# F28335_AddOn_Memory.net
KiCad netlist of a schematic drawn in Altium Designer
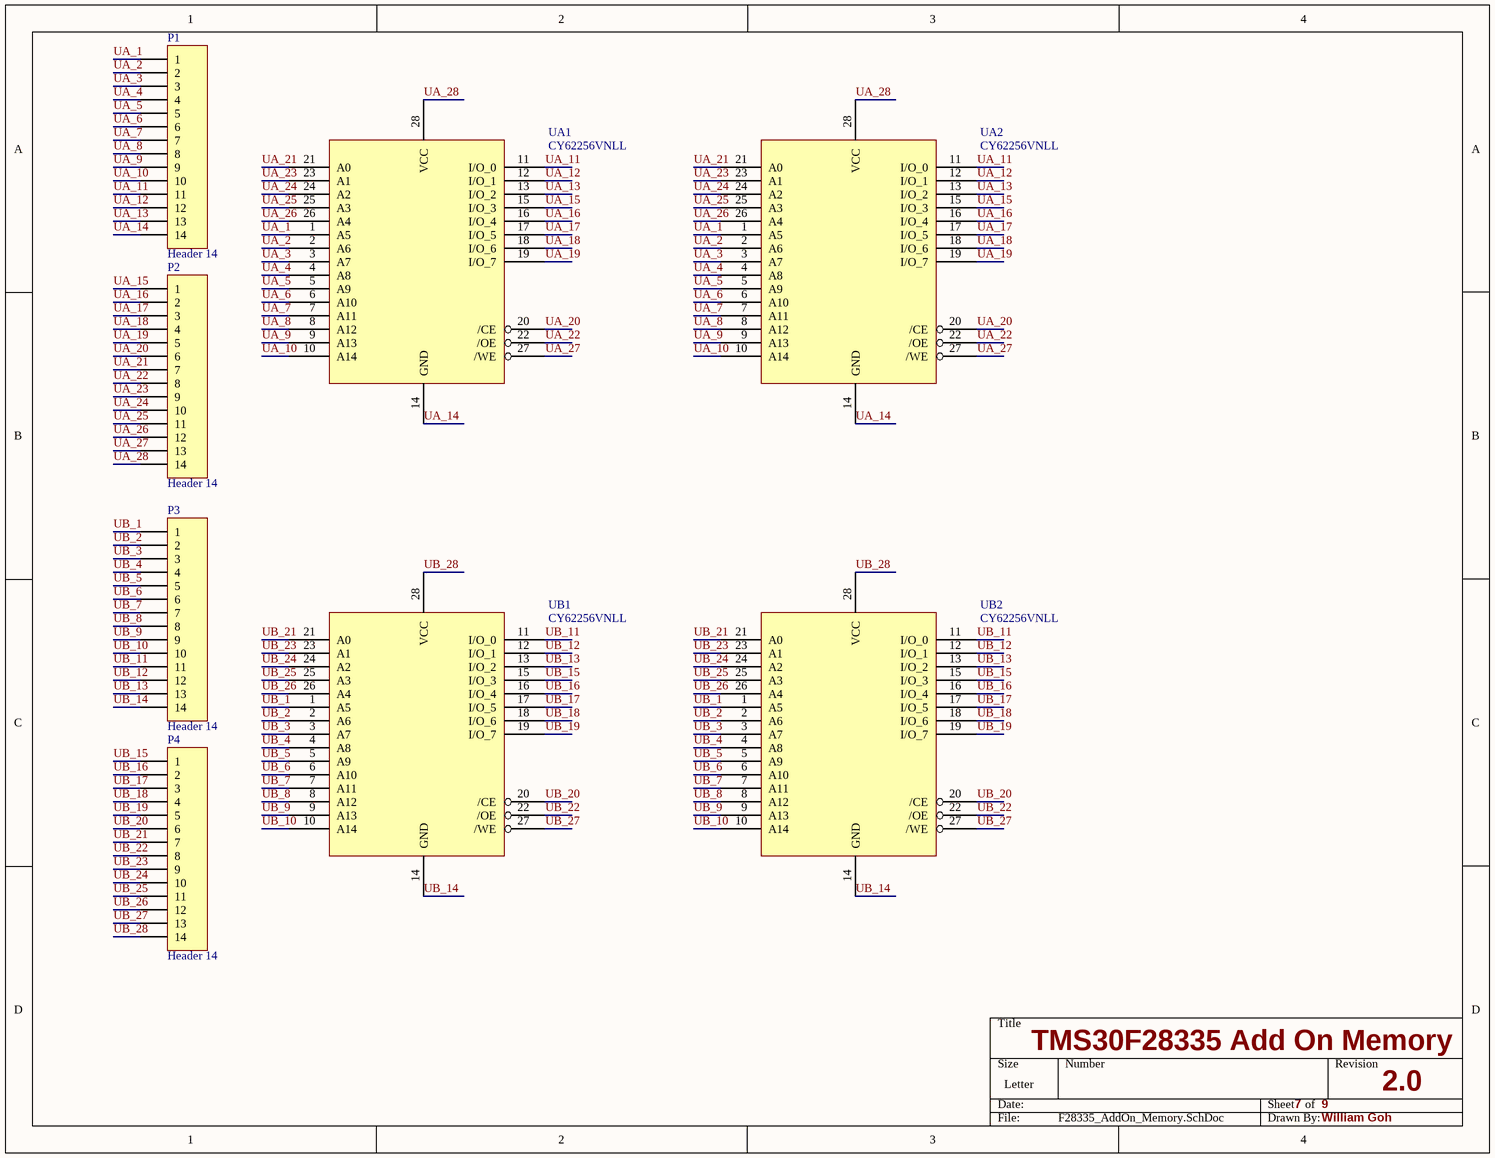
[diagram p0: F28335_AddOn_Memory.SchDoc]

(export (version "E")
  (design (tool "Eeschema 10.0.6"))
  (components
    (comp (ref "P1")
      (value "Header 14")
      (footprint "HDR1X14")
      (description "Header, 14-Pin")
      (fields (field (name "PUBLISHER") "Altium Limited"))
      (libsource (lib "Miscellaneous Connectors") (part "Header 14"))
    )
    (comp (ref "P2")
      (value "Header 14")
      (footprint "HDR1X14")
      (description "Header, 14-Pin")
      (fields (field (name "PUBLISHER") "Altium Limited"))
      (libsource (lib "Miscellaneous Connectors") (part "Header 14"))
    )
    (comp (ref "P3")
      (value "Header 14")
      (footprint "HDR1X14")
      (description "Header, 14-Pin")
      (fields (field (name "PUBLISHER") "Altium Limited"))
      (libsource (lib "Miscellaneous Connectors") (part "Header 14"))
    )
    (comp (ref "P4")
      (value "Header 14")
      (footprint "HDR1X14")
      (description "Header, 14-Pin")
      (fields (field (name "PUBLISHER") "Altium Limited"))
      (libsource (lib "Miscellaneous Connectors") (part "Header 14"))
    )
    (comp (ref "UA1")
      (value "CY62256VNLL")
      (footprint "28-SOIC CY62256VNLL")
      (description "Cypress SRAM 256KB 3.3V")
      (libsource (lib "F28335_DSC_Breakout") (part "CY62256VNLL"))
    )
    (comp (ref "UA2")
      (value "CY62256VNLL")
      (footprint "28-TSSOP CY62256VNLL")
      (description "Cypress SRAM 256KB 3.3V")
      (libsource (lib "F28335_DSC_Breakout") (part "CY62256VNLL"))
    )
    (comp (ref "UB1")
      (value "CY62256VNLL")
      (footprint "28-SOIC CY62256VNLL")
      (description "Cypress SRAM 256KB 3.3V")
      (libsource (lib "F28335_DSC_Breakout") (part "CY62256VNLL"))
    )
    (comp (ref "UB2")
      (value "CY62256VNLL")
      (footprint "28-TSSOP CY62256VNLL")
      (description "Cypress SRAM 256KB 3.3V")
      (libsource (lib "F28335_DSC_Breakout") (part "CY62256VNLL"))
    )
  )
  (nets
    (net (code "1") (name "/UA_1") (class "Default")
      (node (ref "P1") (pin "1") (pinfunction "1_1") (pintype "passive"))
      (node (ref "UA1") (pin "1") (pinfunction "A5_1") (pintype "passive"))
      (node (ref "UA2") (pin "1") (pinfunction "A5_1") (pintype "passive"))
    )
    (net (code "2") (name "/UA_2") (class "Default")
      (node (ref "P1") (pin "2") (pinfunction "2_2") (pintype "passive"))
      (node (ref "UA1") (pin "2") (pinfunction "A6_2") (pintype "passive"))
      (node (ref "UA2") (pin "2") (pinfunction "A6_2") (pintype "passive"))
    )
    (net (code "3") (name "/UA_3") (class "Default")
      (node (ref "P1") (pin "3") (pinfunction "3_3") (pintype "passive"))
      (node (ref "UA1") (pin "3") (pinfunction "A7_3") (pintype "passive"))
      (node (ref "UA2") (pin "3") (pinfunction "A7_3") (pintype "passive"))
    )
    (net (code "4") (name "/UA_4") (class "Default")
      (node (ref "P1") (pin "4") (pinfunction "4_4") (pintype "passive"))
      (node (ref "UA1") (pin "4") (pinfunction "A8_4") (pintype "passive"))
      (node (ref "UA2") (pin "4") (pinfunction "A8_4") (pintype "passive"))
    )
    (net (code "5") (name "/UA_5") (class "Default")
      (node (ref "P1") (pin "5") (pinfunction "5_5") (pintype "passive"))
      (node (ref "UA1") (pin "5") (pinfunction "A9_5") (pintype "passive"))
      (node (ref "UA2") (pin "5") (pinfunction "A9_5") (pintype "passive"))
    )
    (net (code "6") (name "/UA_6") (class "Default")
      (node (ref "P1") (pin "6") (pinfunction "6_6") (pintype "passive"))
      (node (ref "UA1") (pin "6") (pinfunction "A10_6") (pintype "passive"))
      (node (ref "UA2") (pin "6") (pinfunction "A10_6") (pintype "passive"))
    )
    (net (code "7") (name "/UA_7") (class "Default")
      (node (ref "P1") (pin "7") (pinfunction "7_7") (pintype "passive"))
      (node (ref "UA1") (pin "7") (pinfunction "A11_7") (pintype "passive"))
      (node (ref "UA2") (pin "7") (pinfunction "A11_7") (pintype "passive"))
    )
    (net (code "8") (name "/UA_8") (class "Default")
      (node (ref "P1") (pin "8") (pinfunction "8_8") (pintype "passive"))
      (node (ref "UA1") (pin "8") (pinfunction "A12_8") (pintype "passive"))
      (node (ref "UA2") (pin "8") (pinfunction "A12_8") (pintype "passive"))
    )
    (net (code "9") (name "/UA_9") (class "Default")
      (node (ref "P1") (pin "9") (pinfunction "9_9") (pintype "passive"))
      (node (ref "UA1") (pin "9") (pinfunction "A13_9") (pintype "passive"))
      (node (ref "UA2") (pin "9") (pinfunction "A13_9") (pintype "passive"))
    )
    (net (code "10") (name "/UA_10") (class "Default")
      (node (ref "P1") (pin "10") (pinfunction "10_10") (pintype "passive"))
      (node (ref "UA1") (pin "10") (pinfunction "A14_10") (pintype "passive"))
      (node (ref "UA2") (pin "10") (pinfunction "A14_10") (pintype "passive"))
    )
    (net (code "11") (name "/UA_11") (class "Default")
      (node (ref "P1") (pin "11") (pinfunction "11_11") (pintype "passive"))
      (node (ref "UA1") (pin "11") (pinfunction "I/O_0_11") (pintype "passive"))
      (node (ref "UA2") (pin "11") (pinfunction "I/O_0_11") (pintype "passive"))
    )
    (net (code "12") (name "/UA_12") (class "Default")
      (node (ref "P1") (pin "12") (pinfunction "12_12") (pintype "passive"))
      (node (ref "UA1") (pin "12") (pinfunction "I/O_1_12") (pintype "passive"))
      (node (ref "UA2") (pin "12") (pinfunction "I/O_1_12") (pintype "passive"))
    )
    (net (code "13") (name "/UA_13") (class "Default")
      (node (ref "P1") (pin "13") (pinfunction "13_13") (pintype "passive"))
      (node (ref "UA1") (pin "13") (pinfunction "I/O_2_13") (pintype "passive"))
      (node (ref "UA2") (pin "13") (pinfunction "I/O_2_13") (pintype "passive"))
    )
    (net (code "14") (name "/UA_14") (class "Default")
      (node (ref "P1") (pin "14") (pinfunction "14_14") (pintype "passive"))
      (node (ref "UA1") (pin "14") (pinfunction "GND_14") (pintype "passive"))
      (node (ref "UA2") (pin "14") (pinfunction "GND_14") (pintype "passive"))
    )
    (net (code "15") (name "/UA_15") (class "Default")
      (node (ref "P2") (pin "1") (pinfunction "1_1") (pintype "passive"))
      (node (ref "UA1") (pin "15") (pinfunction "I/O_3_15") (pintype "passive"))
      (node (ref "UA2") (pin "15") (pinfunction "I/O_3_15") (pintype "passive"))
    )
    (net (code "16") (name "/UA_16") (class "Default")
      (node (ref "P2") (pin "2") (pinfunction "2_2") (pintype "passive"))
      (node (ref "UA1") (pin "16") (pinfunction "I/O_4_16") (pintype "passive"))
      (node (ref "UA2") (pin "16") (pinfunction "I/O_4_16") (pintype "passive"))
    )
    (net (code "17") (name "/UA_17") (class "Default")
      (node (ref "P2") (pin "3") (pinfunction "3_3") (pintype "passive"))
      (node (ref "UA1") (pin "17") (pinfunction "I/O_5_17") (pintype "passive"))
      (node (ref "UA2") (pin "17") (pinfunction "I/O_5_17") (pintype "passive"))
    )
    (net (code "18") (name "/UA_18") (class "Default")
      (node (ref "P2") (pin "4") (pinfunction "4_4") (pintype "passive"))
      (node (ref "UA1") (pin "18") (pinfunction "I/O_6_18") (pintype "passive"))
      (node (ref "UA2") (pin "18") (pinfunction "I/O_6_18") (pintype "passive"))
    )
    (net (code "19") (name "/UA_19") (class "Default")
      (node (ref "P2") (pin "5") (pinfunction "5_5") (pintype "passive"))
      (node (ref "UA1") (pin "19") (pinfunction "I/O_7_19") (pintype "passive"))
      (node (ref "UA2") (pin "19") (pinfunction "I/O_7_19") (pintype "passive"))
    )
    (net (code "20") (name "/UA_20") (class "Default")
      (node (ref "P2") (pin "6") (pinfunction "6_6") (pintype "passive"))
      (node (ref "UA1") (pin "20") (pinfunction "/CE_20") (pintype "passive"))
      (node (ref "UA2") (pin "20") (pinfunction "/CE_20") (pintype "passive"))
    )
    (net (code "21") (name "/UA_21") (class "Default")
      (node (ref "P2") (pin "7") (pinfunction "7_7") (pintype "passive"))
      (node (ref "UA1") (pin "21") (pinfunction "A0_21") (pintype "passive"))
      (node (ref "UA2") (pin "21") (pinfunction "A0_21") (pintype "passive"))
    )
    (net (code "22") (name "/UA_22") (class "Default")
      (node (ref "P2") (pin "8") (pinfunction "8_8") (pintype "passive"))
      (node (ref "UA1") (pin "22") (pinfunction "/OE_22") (pintype "passive"))
      (node (ref "UA2") (pin "22") (pinfunction "/OE_22") (pintype "passive"))
    )
    (net (code "23") (name "/UA_23") (class "Default")
      (node (ref "P2") (pin "9") (pinfunction "9_9") (pintype "passive"))
      (node (ref "UA1") (pin "23") (pinfunction "A1_23") (pintype "passive"))
      (node (ref "UA2") (pin "23") (pinfunction "A1_23") (pintype "passive"))
    )
    (net (code "24") (name "/UA_24") (class "Default")
      (node (ref "P2") (pin "10") (pinfunction "10_10") (pintype "passive"))
      (node (ref "UA1") (pin "24") (pinfunction "A2_24") (pintype "passive"))
      (node (ref "UA2") (pin "24") (pinfunction "A2_24") (pintype "passive"))
    )
    (net (code "25") (name "/UA_25") (class "Default")
      (node (ref "P2") (pin "11") (pinfunction "11_11") (pintype "passive"))
      (node (ref "UA1") (pin "25") (pinfunction "A3_25") (pintype "passive"))
      (node (ref "UA2") (pin "25") (pinfunction "A3_25") (pintype "passive"))
    )
    (net (code "26") (name "/UA_26") (class "Default")
      (node (ref "P2") (pin "12") (pinfunction "12_12") (pintype "passive"))
      (node (ref "UA1") (pin "26") (pinfunction "A4_26") (pintype "passive"))
      (node (ref "UA2") (pin "26") (pinfunction "A4_26") (pintype "passive"))
    )
    (net (code "27") (name "/UA_27") (class "Default")
      (node (ref "P2") (pin "13") (pinfunction "13_13") (pintype "passive"))
      (node (ref "UA1") (pin "27") (pinfunction "/WE_27") (pintype "passive"))
      (node (ref "UA2") (pin "27") (pinfunction "/WE_27") (pintype "passive"))
    )
    (net (code "28") (name "/UA_28") (class "Default")
      (node (ref "P2") (pin "14") (pinfunction "14_14") (pintype "passive"))
      (node (ref "UA1") (pin "28") (pinfunction "VCC_28") (pintype "passive"))
      (node (ref "UA2") (pin "28") (pinfunction "VCC_28") (pintype "passive"))
    )
    (net (code "29") (name "/UB_1") (class "Default")
      (node (ref "P3") (pin "1") (pinfunction "1_1") (pintype "passive"))
      (node (ref "UB1") (pin "1") (pinfunction "A5_1") (pintype "passive"))
      (node (ref "UB2") (pin "1") (pinfunction "A5_1") (pintype "passive"))
    )
    (net (code "30") (name "/UB_2") (class "Default")
      (node (ref "P3") (pin "2") (pinfunction "2_2") (pintype "passive"))
      (node (ref "UB1") (pin "2") (pinfunction "A6_2") (pintype "passive"))
      (node (ref "UB2") (pin "2") (pinfunction "A6_2") (pintype "passive"))
    )
    (net (code "31") (name "/UB_3") (class "Default")
      (node (ref "P3") (pin "3") (pinfunction "3_3") (pintype "passive"))
      (node (ref "UB1") (pin "3") (pinfunction "A7_3") (pintype "passive"))
      (node (ref "UB2") (pin "3") (pinfunction "A7_3") (pintype "passive"))
    )
    (net (code "32") (name "/UB_4") (class "Default")
      (node (ref "P3") (pin "4") (pinfunction "4_4") (pintype "passive"))
      (node (ref "UB1") (pin "4") (pinfunction "A8_4") (pintype "passive"))
      (node (ref "UB2") (pin "4") (pinfunction "A8_4") (pintype "passive"))
    )
    (net (code "33") (name "/UB_5") (class "Default")
      (node (ref "P3") (pin "5") (pinfunction "5_5") (pintype "passive"))
      (node (ref "UB1") (pin "5") (pinfunction "A9_5") (pintype "passive"))
      (node (ref "UB2") (pin "5") (pinfunction "A9_5") (pintype "passive"))
    )
    (net (code "34") (name "/UB_6") (class "Default")
      (node (ref "P3") (pin "6") (pinfunction "6_6") (pintype "passive"))
      (node (ref "UB1") (pin "6") (pinfunction "A10_6") (pintype "passive"))
      (node (ref "UB2") (pin "6") (pinfunction "A10_6") (pintype "passive"))
    )
    (net (code "35") (name "/UB_7") (class "Default")
      (node (ref "P3") (pin "7") (pinfunction "7_7") (pintype "passive"))
      (node (ref "UB1") (pin "7") (pinfunction "A11_7") (pintype "passive"))
      (node (ref "UB2") (pin "7") (pinfunction "A11_7") (pintype "passive"))
    )
    (net (code "36") (name "/UB_8") (class "Default")
      (node (ref "P3") (pin "8") (pinfunction "8_8") (pintype "passive"))
      (node (ref "UB1") (pin "8") (pinfunction "A12_8") (pintype "passive"))
      (node (ref "UB2") (pin "8") (pinfunction "A12_8") (pintype "passive"))
    )
    (net (code "37") (name "/UB_9") (class "Default")
      (node (ref "P3") (pin "9") (pinfunction "9_9") (pintype "passive"))
      (node (ref "UB1") (pin "9") (pinfunction "A13_9") (pintype "passive"))
      (node (ref "UB2") (pin "9") (pinfunction "A13_9") (pintype "passive"))
    )
    (net (code "38") (name "/UB_10") (class "Default")
      (node (ref "P3") (pin "10") (pinfunction "10_10") (pintype "passive"))
      (node (ref "UB1") (pin "10") (pinfunction "A14_10") (pintype "passive"))
      (node (ref "UB2") (pin "10") (pinfunction "A14_10") (pintype "passive"))
    )
    (net (code "39") (name "/UB_11") (class "Default")
      (node (ref "P3") (pin "11") (pinfunction "11_11") (pintype "passive"))
      (node (ref "UB1") (pin "11") (pinfunction "I/O_0_11") (pintype "passive"))
      (node (ref "UB2") (pin "11") (pinfunction "I/O_0_11") (pintype "passive"))
    )
    (net (code "40") (name "/UB_12") (class "Default")
      (node (ref "P3") (pin "12") (pinfunction "12_12") (pintype "passive"))
      (node (ref "UB1") (pin "12") (pinfunction "I/O_1_12") (pintype "passive"))
      (node (ref "UB2") (pin "12") (pinfunction "I/O_1_12") (pintype "passive"))
    )
    (net (code "41") (name "/UB_13") (class "Default")
      (node (ref "P3") (pin "13") (pinfunction "13_13") (pintype "passive"))
      (node (ref "UB1") (pin "13") (pinfunction "I/O_2_13") (pintype "passive"))
      (node (ref "UB2") (pin "13") (pinfunction "I/O_2_13") (pintype "passive"))
    )
    (net (code "42") (name "/UB_14") (class "Default")
      (node (ref "P3") (pin "14") (pinfunction "14_14") (pintype "passive"))
      (node (ref "UB1") (pin "14") (pinfunction "GND_14") (pintype "passive"))
      (node (ref "UB2") (pin "14") (pinfunction "GND_14") (pintype "passive"))
    )
    (net (code "43") (name "/UB_15") (class "Default")
      (node (ref "P4") (pin "1") (pinfunction "1_1") (pintype "passive"))
      (node (ref "UB1") (pin "15") (pinfunction "I/O_3_15") (pintype "passive"))
      (node (ref "UB2") (pin "15") (pinfunction "I/O_3_15") (pintype "passive"))
    )
    (net (code "44") (name "/UB_16") (class "Default")
      (node (ref "P4") (pin "2") (pinfunction "2_2") (pintype "passive"))
      (node (ref "UB1") (pin "16") (pinfunction "I/O_4_16") (pintype "passive"))
      (node (ref "UB2") (pin "16") (pinfunction "I/O_4_16") (pintype "passive"))
    )
    (net (code "45") (name "/UB_17") (class "Default")
      (node (ref "P4") (pin "3") (pinfunction "3_3") (pintype "passive"))
      (node (ref "UB1") (pin "17") (pinfunction "I/O_5_17") (pintype "passive"))
      (node (ref "UB2") (pin "17") (pinfunction "I/O_5_17") (pintype "passive"))
    )
    (net (code "46") (name "/UB_18") (class "Default")
      (node (ref "P4") (pin "4") (pinfunction "4_4") (pintype "passive"))
      (node (ref "UB1") (pin "18") (pinfunction "I/O_6_18") (pintype "passive"))
      (node (ref "UB2") (pin "18") (pinfunction "I/O_6_18") (pintype "passive"))
    )
    (net (code "47") (name "/UB_19") (class "Default")
      (node (ref "P4") (pin "5") (pinfunction "5_5") (pintype "passive"))
      (node (ref "UB1") (pin "19") (pinfunction "I/O_7_19") (pintype "passive"))
      (node (ref "UB2") (pin "19") (pinfunction "I/O_7_19") (pintype "passive"))
    )
    (net (code "48") (name "/UB_20") (class "Default")
      (node (ref "P4") (pin "6") (pinfunction "6_6") (pintype "passive"))
      (node (ref "UB1") (pin "20") (pinfunction "/CE_20") (pintype "passive"))
      (node (ref "UB2") (pin "20") (pinfunction "/CE_20") (pintype "passive"))
    )
    (net (code "49") (name "/UB_21") (class "Default")
      (node (ref "P4") (pin "7") (pinfunction "7_7") (pintype "passive"))
      (node (ref "UB1") (pin "21") (pinfunction "A0_21") (pintype "passive"))
      (node (ref "UB2") (pin "21") (pinfunction "A0_21") (pintype "passive"))
    )
    (net (code "50") (name "/UB_22") (class "Default")
      (node (ref "P4") (pin "8") (pinfunction "8_8") (pintype "passive"))
      (node (ref "UB1") (pin "22") (pinfunction "/OE_22") (pintype "passive"))
      (node (ref "UB2") (pin "22") (pinfunction "/OE_22") (pintype "passive"))
    )
    (net (code "51") (name "/UB_23") (class "Default")
      (node (ref "P4") (pin "9") (pinfunction "9_9") (pintype "passive"))
      (node (ref "UB1") (pin "23") (pinfunction "A1_23") (pintype "passive"))
      (node (ref "UB2") (pin "23") (pinfunction "A1_23") (pintype "passive"))
    )
    (net (code "52") (name "/UB_24") (class "Default")
      (node (ref "P4") (pin "10") (pinfunction "10_10") (pintype "passive"))
      (node (ref "UB1") (pin "24") (pinfunction "A2_24") (pintype "passive"))
      (node (ref "UB2") (pin "24") (pinfunction "A2_24") (pintype "passive"))
    )
    (net (code "53") (name "/UB_25") (class "Default")
      (node (ref "P4") (pin "11") (pinfunction "11_11") (pintype "passive"))
      (node (ref "UB1") (pin "25") (pinfunction "A3_25") (pintype "passive"))
      (node (ref "UB2") (pin "25") (pinfunction "A3_25") (pintype "passive"))
    )
    (net (code "54") (name "/UB_26") (class "Default")
      (node (ref "P4") (pin "12") (pinfunction "12_12") (pintype "passive"))
      (node (ref "UB1") (pin "26") (pinfunction "A4_26") (pintype "passive"))
      (node (ref "UB2") (pin "26") (pinfunction "A4_26") (pintype "passive"))
    )
    (net (code "55") (name "/UB_27") (class "Default")
      (node (ref "P4") (pin "13") (pinfunction "13_13") (pintype "passive"))
      (node (ref "UB1") (pin "27") (pinfunction "/WE_27") (pintype "passive"))
      (node (ref "UB2") (pin "27") (pinfunction "/WE_27") (pintype "passive"))
    )
    (net (code "56") (name "/UB_28") (class "Default")
      (node (ref "P4") (pin "14") (pinfunction "14_14") (pintype "passive"))
      (node (ref "UB1") (pin "28") (pinfunction "VCC_28") (pintype "passive"))
      (node (ref "UB2") (pin "28") (pinfunction "VCC_28") (pintype "passive"))
    )
  )
)
